# powerAMP.net
KiCad netlist of a schematic drawn in EAGLE
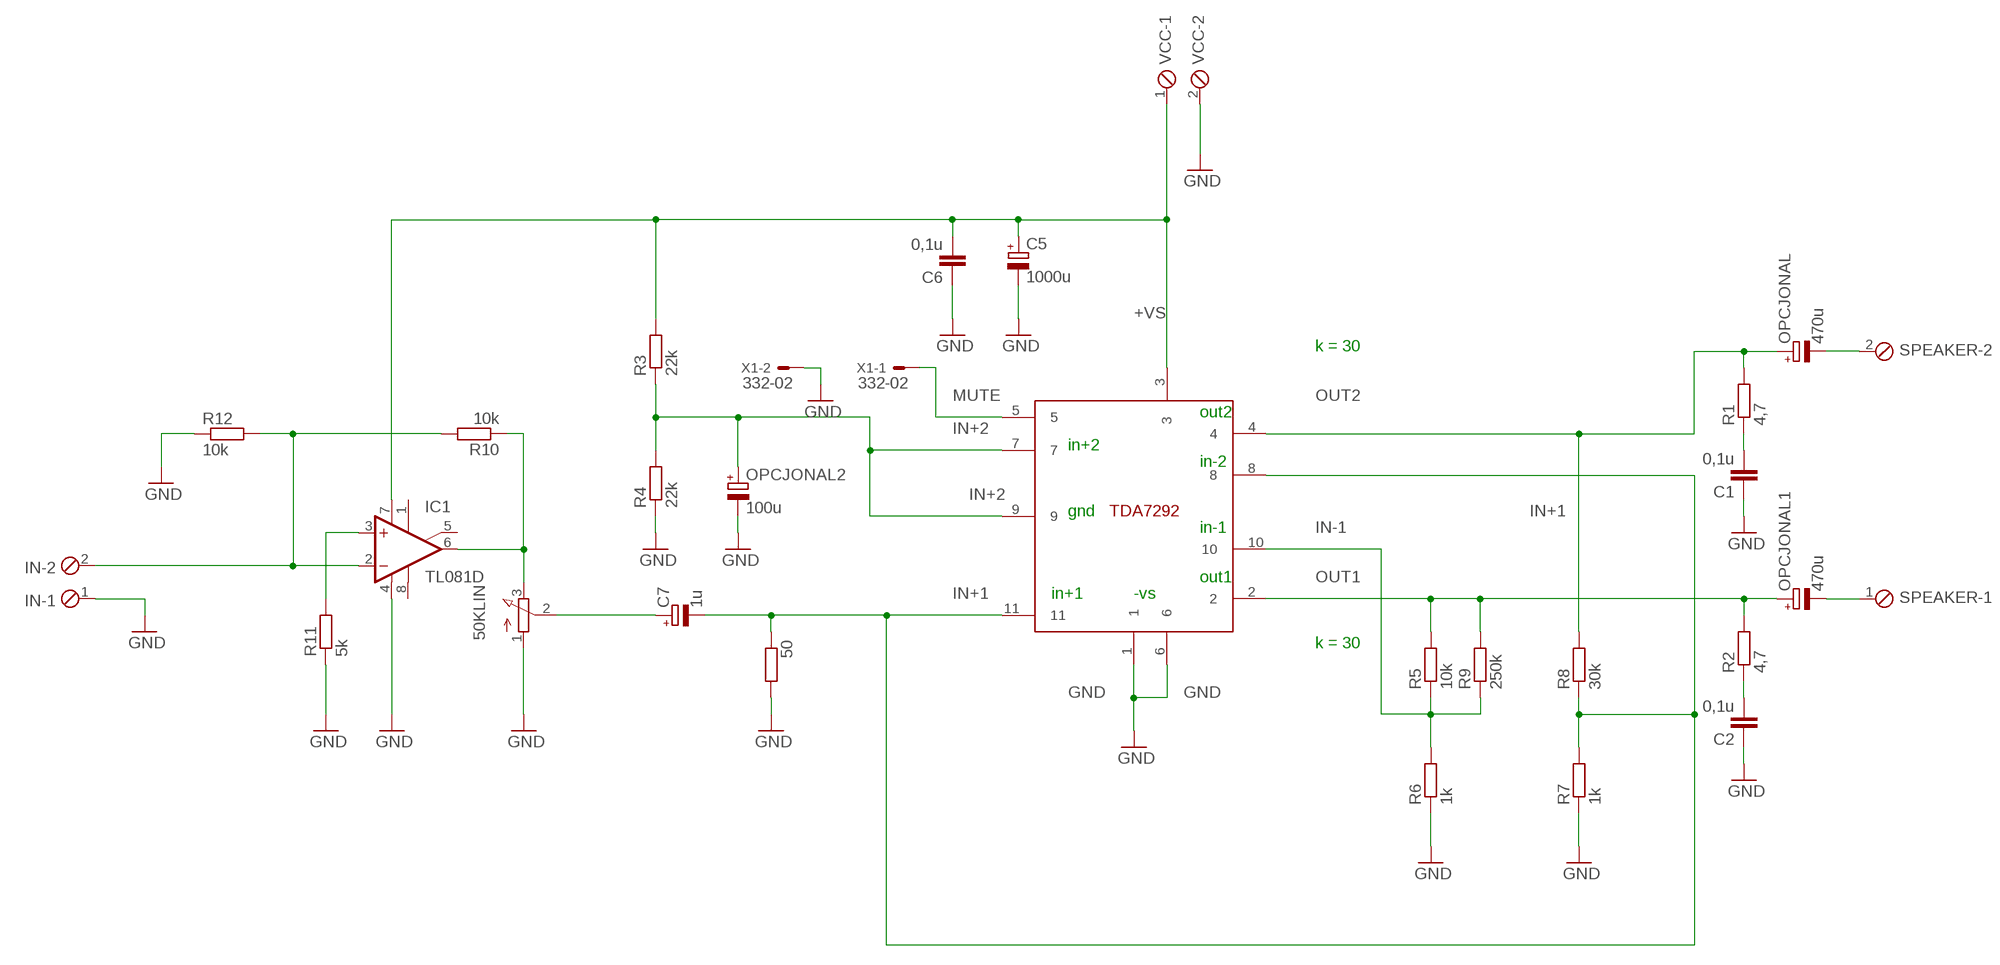
[diagram p0: schematic, sheet 1]

(export (version "E")
  (design (tool "Eeschema 10.0.6"))
  (components
    (comp (ref "50")
      (value "R-EU_M0805")
      (footprint "eagle-import:M0805")
      (libsource (lib "eagle-import") (part "R-EU_M0805"))
    )
    (comp (ref "50KLIN")
      (value "3RP/1610N")
      (footprint "eagle-import:3RP_1610N")
      (libsource (lib "eagle-import") (part "3RP/1610N"))
    )
    (comp (ref "C1")
      (value "0,1u")
      (footprint "eagle-import:C1206")
      (libsource (lib "eagle-import") (part "C-EUC1206"))
    )
    (comp (ref "C2")
      (value "0,1u")
      (footprint "eagle-import:C1206")
      (libsource (lib "eagle-import") (part "C-EUC1206"))
    )
    (comp (ref "C5")
      (value "1000u")
      (footprint "eagle-import:E2,5-7")
      (libsource (lib "eagle-import") (part "CPOL-EUE2.5-7"))
    )
    (comp (ref "C6")
      (value "0,1u")
      (footprint "eagle-import:C1206")
      (libsource (lib "eagle-import") (part "C-EUC1206"))
    )
    (comp (ref "C7")
      (value "1u")
      (footprint "eagle-import:E2,5-5")
      (libsource (lib "eagle-import") (part "CPOL-EUE2.5-5"))
    )
    (comp (ref "IC1")
      (value "TL081D")
      (footprint "eagle-import:SO08")
      (libsource (lib "eagle-import") (part "TL081D"))
    )
    (comp (ref "IN")
      (value "MPT2")
      (footprint "eagle-import:2POL254")
      (libsource (lib "eagle-import") (part "MPT2"))
    )
    (comp (ref "OPCJONAL")
      (value "470u")
      (footprint "eagle-import:E2,5-7")
      (libsource (lib "eagle-import") (part "CPOL-EUE2.5-7"))
    )
    (comp (ref "OPCJONAL1")
      (value "470u")
      (footprint "eagle-import:E2,5-7")
      (libsource (lib "eagle-import") (part "CPOL-EUE2.5-7"))
    )
    (comp (ref "OPCJONAL2")
      (value "100u")
      (footprint "eagle-import:E2,5-7")
      (libsource (lib "eagle-import") (part "CPOL-EUE2.5-7"))
    )
    (comp (ref "R1")
      (value "4,7")
      (footprint "eagle-import:M0805")
      (libsource (lib "eagle-import") (part "R-EU_M0805"))
    )
    (comp (ref "R2")
      (value "4,7")
      (footprint "eagle-import:M0805")
      (libsource (lib "eagle-import") (part "R-EU_M0805"))
    )
    (comp (ref "R3")
      (value "22k")
      (footprint "eagle-import:M0805")
      (libsource (lib "eagle-import") (part "R-EU_M0805"))
    )
    (comp (ref "R4")
      (value "22k")
      (footprint "eagle-import:M0805")
      (libsource (lib "eagle-import") (part "R-EU_M0805"))
    )
    (comp (ref "R5")
      (value "10k")
      (footprint "eagle-import:M0805")
      (libsource (lib "eagle-import") (part "R-EU_M0805"))
    )
    (comp (ref "R6")
      (value "1k")
      (footprint "eagle-import:M0805")
      (libsource (lib "eagle-import") (part "R-EU_M0805"))
    )
    (comp (ref "R7")
      (value "1k")
      (footprint "eagle-import:M0805")
      (libsource (lib "eagle-import") (part "R-EU_M0805"))
    )
    (comp (ref "R8")
      (value "30k")
      (footprint "eagle-import:M0805")
      (libsource (lib "eagle-import") (part "R-EU_M0805"))
    )
    (comp (ref "R9")
      (value "250k")
      (footprint "eagle-import:M0805")
      (libsource (lib "eagle-import") (part "R-EU_M0805"))
    )
    (comp (ref "R10")
      (value "10k")
      (footprint "eagle-import:M0805")
      (libsource (lib "eagle-import") (part "R-EU_M0805"))
    )
    (comp (ref "R11")
      (value "5k")
      (footprint "eagle-import:M0805")
      (libsource (lib "eagle-import") (part "R-EU_M0805"))
    )
    (comp (ref "R12")
      (value "10k")
      (footprint "eagle-import:M0805")
      (libsource (lib "eagle-import") (part "R-EU_M0805"))
    )
    (comp (ref "SPEAKER")
      (value "MPT2")
      (footprint "eagle-import:2POL254")
      (libsource (lib "eagle-import") (part "MPT2"))
    )
    (comp (ref "U$1")
      (value "TDA7292TDA7292")
      (footprint "eagle-import:MULTIWATT11")
      (libsource (lib "eagle-import") (part "TDA7292TDA7292"))
    )
    (comp (ref "VCC")
      (value "MPT2")
      (footprint "eagle-import:2POL254")
      (libsource (lib "eagle-import") (part "MPT2"))
    )
    (comp (ref "X1")
      (value "332-02")
      (footprint "eagle-import:332-02")
      (libsource (lib "eagle-import") (part "332-02"))
    )
  )
  (nets
    (net (code "1") (name "/+VS") (class "Default")
      (node (ref "C5") (pin "+") (pinfunction "+_+") (pintype "passive"))
      (node (ref "C6") (pin "2") (pinfunction "2_2") (pintype "passive"))
      (node (ref "IC1") (pin "7") (pinfunction "V+_7") (pintype "power_in"))
      (node (ref "R3") (pin "2") (pinfunction "2_2") (pintype "passive"))
      (node (ref "U$1") (pin "3") (pinfunction "3_3") (pintype "bidirectional"))
      (node (ref "VCC") (pin "1") (pinfunction "1_1") (pintype "passive"))
    )
    (net (code "2") (name "/IN+1") (class "Default")
      (node (ref "50") (pin "1") (pinfunction "1_1") (pintype "passive"))
      (node (ref "C7") (pin "-") (pinfunction "-_-") (pintype "passive"))
      (node (ref "R7") (pin "2") (pinfunction "2_2") (pintype "passive"))
      (node (ref "R8") (pin "1") (pinfunction "1_1") (pintype "passive"))
      (node (ref "U$1") (pin "11") (pinfunction "11_11") (pintype "bidirectional"))
      (node (ref "U$1") (pin "8") (pinfunction "8_8") (pintype "bidirectional"))
    )
    (net (code "3") (name "/IN+2") (class "Default")
      (node (ref "OPCJONAL2") (pin "+") (pinfunction "+_+") (pintype "passive"))
      (node (ref "R3") (pin "1") (pinfunction "1_1") (pintype "passive"))
      (node (ref "R4") (pin "2") (pinfunction "2_2") (pintype "passive"))
      (node (ref "U$1") (pin "7") (pinfunction "7_7") (pintype "bidirectional"))
      (node (ref "U$1") (pin "9") (pinfunction "9_9") (pintype "bidirectional"))
    )
    (net (code "4") (name "/IN-1") (class "Default")
      (node (ref "R5") (pin "1") (pinfunction "1_1") (pintype "passive"))
      (node (ref "R6") (pin "2") (pinfunction "2_2") (pintype "passive"))
      (node (ref "R9") (pin "1") (pinfunction "1_1") (pintype "passive"))
      (node (ref "U$1") (pin "10") (pinfunction "10_10") (pintype "bidirectional"))
    )
    (net (code "5") (name "/MUTE") (class "Default")
      (node (ref "U$1") (pin "5") (pinfunction "5_5") (pintype "bidirectional"))
      (node (ref "X1") (pin "1") (pinfunction "S_1") (pintype "passive"))
    )
    (net (code "6") (name "/OUT1") (class "Default")
      (node (ref "OPCJONAL1") (pin "+") (pinfunction "+_+") (pintype "passive"))
      (node (ref "R2") (pin "2") (pinfunction "2_2") (pintype "passive"))
      (node (ref "R5") (pin "2") (pinfunction "2_2") (pintype "passive"))
      (node (ref "R9") (pin "2") (pinfunction "2_2") (pintype "passive"))
      (node (ref "U$1") (pin "2") (pinfunction "2_2") (pintype "bidirectional"))
    )
    (net (code "7") (name "/OUT2") (class "Default")
      (node (ref "OPCJONAL") (pin "+") (pinfunction "+_+") (pintype "passive"))
      (node (ref "R1") (pin "2") (pinfunction "2_2") (pintype "passive"))
      (node (ref "R8") (pin "2") (pinfunction "2_2") (pintype "passive"))
      (node (ref "U$1") (pin "4") (pinfunction "4_4") (pintype "bidirectional"))
    )
    (net (code "8") (name "GND") (class "Default")
      (node (ref "50") (pin "2") (pinfunction "2_2") (pintype "passive"))
      (node (ref "50KLIN") (pin "1") (pinfunction "A_1") (pintype "passive"))
      (node (ref "C1") (pin "1") (pinfunction "1_1") (pintype "passive"))
      (node (ref "C2") (pin "1") (pinfunction "1_1") (pintype "passive"))
      (node (ref "C5") (pin "-") (pinfunction "-_-") (pintype "passive"))
      (node (ref "C6") (pin "1") (pinfunction "1_1") (pintype "passive"))
      (node (ref "IC1") (pin "4") (pinfunction "V-_4") (pintype "power_in"))
      (node (ref "IN") (pin "1") (pinfunction "1_1") (pintype "passive"))
      (node (ref "OPCJONAL2") (pin "-") (pinfunction "-_-") (pintype "passive"))
      (node (ref "R11") (pin "1") (pinfunction "1_1") (pintype "passive"))
      (node (ref "R12") (pin "1") (pinfunction "1_1") (pintype "passive"))
      (node (ref "R4") (pin "1") (pinfunction "1_1") (pintype "passive"))
      (node (ref "R6") (pin "1") (pinfunction "1_1") (pintype "passive"))
      (node (ref "R7") (pin "1") (pinfunction "1_1") (pintype "passive"))
      (node (ref "U$1") (pin "1") (pinfunction "1_1") (pintype "bidirectional"))
      (node (ref "U$1") (pin "6") (pinfunction "6_6") (pintype "bidirectional"))
      (node (ref "VCC") (pin "2") (pinfunction "1_2") (pintype "passive"))
      (node (ref "X1") (pin "2") (pinfunction "S_2") (pintype "passive"))
    )
    (net (code "9") (name "Net-(50KLIN-E)") (class "Default")
      (node (ref "50KLIN") (pin "3") (pinfunction "E_3") (pintype "passive"))
      (node (ref "IC1") (pin "6") (pinfunction "OUT_6") (pintype "output"))
      (node (ref "R10") (pin "1") (pinfunction "1_1") (pintype "passive"))
    )
    (net (code "10") (name "Net-(50KLIN-S)") (class "Default")
      (node (ref "50KLIN") (pin "2") (pinfunction "S_2") (pintype "passive"))
      (node (ref "C7") (pin "+") (pinfunction "+_+") (pintype "passive"))
    )
    (net (code "11") (name "Net-(C1-Pad2)") (class "Default")
      (node (ref "C1") (pin "2") (pinfunction "2_2") (pintype "passive"))
      (node (ref "R1") (pin "1") (pinfunction "1_1") (pintype "passive"))
    )
    (net (code "12") (name "Net-(C2-Pad2)") (class "Default")
      (node (ref "C2") (pin "2") (pinfunction "2_2") (pintype "passive"))
      (node (ref "R2") (pin "1") (pinfunction "1_1") (pintype "passive"))
    )
    (net (code "13") (name "Net-(IC1-+IN)") (class "Default")
      (node (ref "IC1") (pin "3") (pinfunction "+IN_3") (pintype "input"))
      (node (ref "R11") (pin "2") (pinfunction "2_2") (pintype "passive"))
    )
    (net (code "14") (name "Net-(IC1--IN)") (class "Default")
      (node (ref "IC1") (pin "2") (pinfunction "-IN_2") (pintype "input"))
      (node (ref "IN") (pin "2") (pinfunction "1_2") (pintype "passive"))
      (node (ref "R10") (pin "2") (pinfunction "2_2") (pintype "passive"))
      (node (ref "R12") (pin "2") (pinfunction "2_2") (pintype "passive"))
    )
    (net (code "15") (name "Net-(OPCJONAL1-Pad-)") (class "Default")
      (node (ref "OPCJONAL1") (pin "-") (pinfunction "-_-") (pintype "passive"))
      (node (ref "SPEAKER") (pin "1") (pinfunction "1_1") (pintype "passive"))
    )
    (net (code "16") (name "Net-(SPEAKERB-1)") (class "Default")
      (node (ref "OPCJONAL") (pin "-") (pinfunction "-_-") (pintype "passive"))
      (node (ref "SPEAKER") (pin "2") (pinfunction "1_2") (pintype "passive"))
    )
    (net (code "17") (name "unconnected-(IC1-ON1-Pad1)") (class "Default")
      (node (ref "IC1") (pin "1") (pinfunction "ON1_1") (pintype "passive"))
    )
    (net (code "18") (name "unconnected-(IC1-ON2-Pad5)") (class "Default")
      (node (ref "IC1") (pin "5") (pinfunction "ON2_5") (pintype "passive"))
    )
    (net (code "19") (name "unconnected-(IC1-OPT-Pad8)") (class "Default")
      (node (ref "IC1") (pin "8") (pinfunction "OPT_8") (pintype "passive"))
    )
  )
)
